# 09_USB_hub.net
KiCad netlist of a schematic drawn in Altium Designer
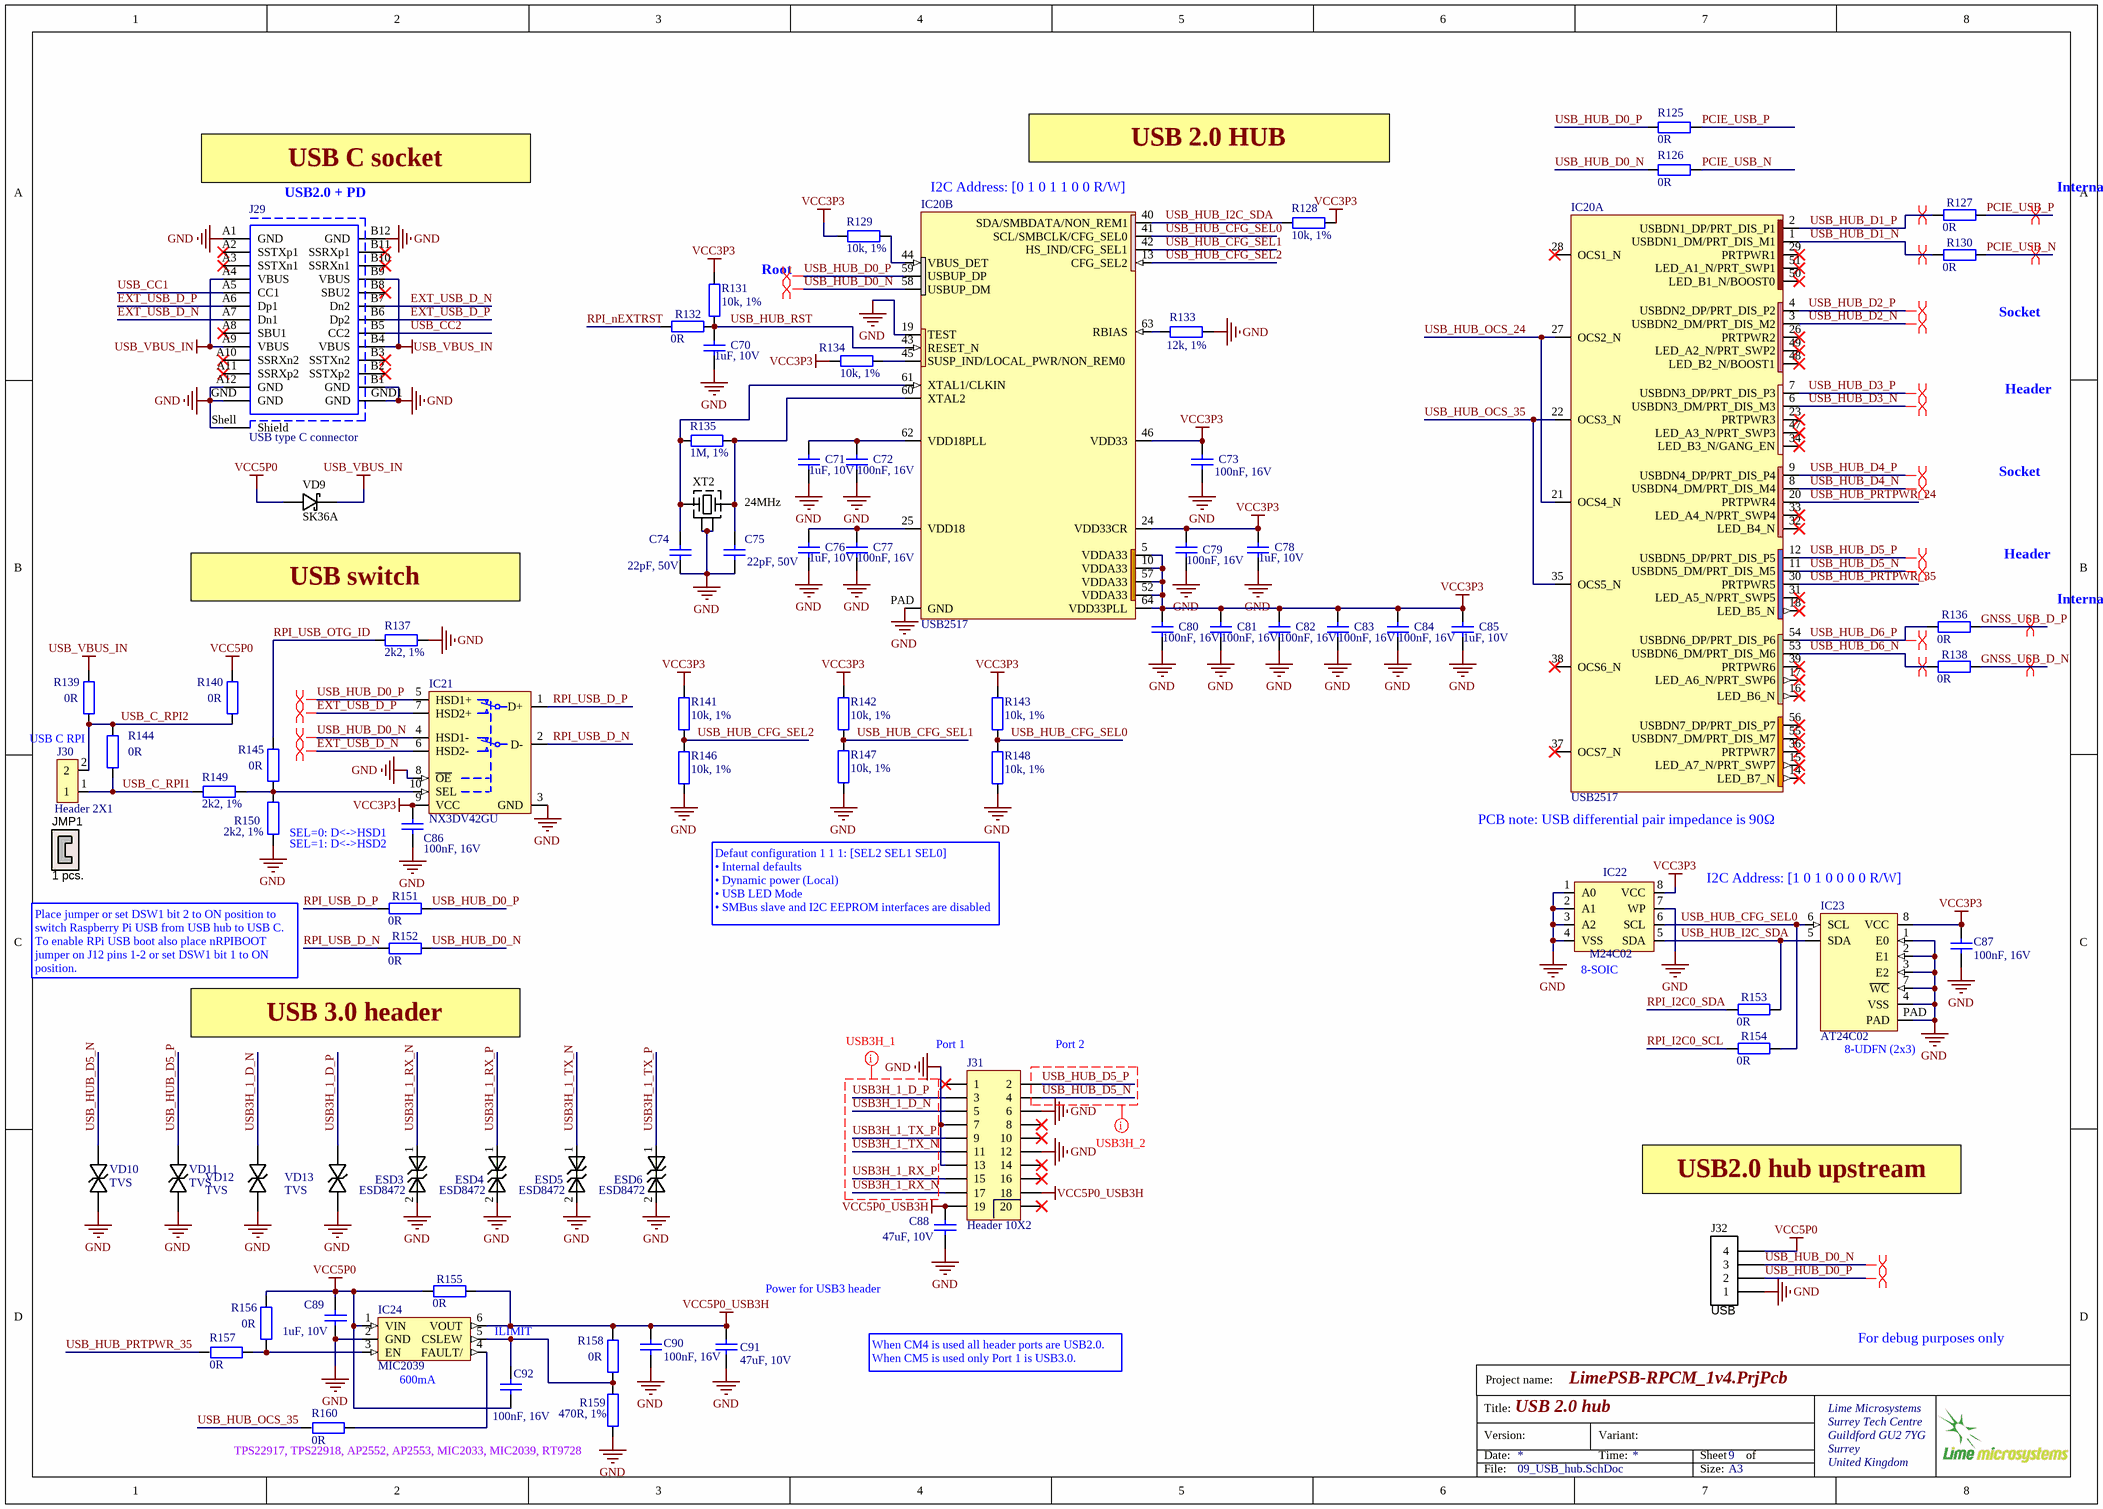
[diagram p0: 09_USB_hub.SchDoc]

(export (version "E")
  (design (tool "Eeschema 10.0.6"))
  (components
    (comp (ref "C70")
      (value "1uF, 10V")
      (footprint "CAP0402")
      (description "CAP CER 1UF 10V X5R 0402")
      (fields (field (name "MANUFACTURER") "Yageo") (field (name "TOLERANCE") "±20%"))
      (libsource (lib "LimeMicroAltiumLib_schLib") (part "Cap_0402"))
    )
    (comp (ref "C71")
      (value "1uF, 10V")
      (footprint "CAP0402")
      (description "CAP CER 1UF 10V X5R 0402")
      (fields (field (name "MANUFACTURER") "Yageo") (field (name "TOLERANCE") "±20%"))
      (libsource (lib "LimeMicroAltiumLib_schLib") (part "Cap_0402"))
    )
    (comp (ref "C72")
      (value "100nF, 16V")
      (footprint "CAP0402")
      (fields
        (field (name "MANUFACTURER") "Murata Electronics")
        (field (name "TOLERANCE") "10 %")
        (field (name "MANUFACTURER PART NUMBER") "GRM155R71C104KA88D")
      )
      (libsource (lib "LimeMicroAltiumLib_schLib") (part "Cap_0402"))
    )
    (comp (ref "C73")
      (value "100nF, 16V")
      (footprint "CAP0402")
      (fields
        (field (name "MANUFACTURER") "Murata Electronics")
        (field (name "TOLERANCE") "10 %")
        (field (name "MANUFACTURER PART NUMBER") "GRM155R71C104KA88D")
      )
      (libsource (lib "LimeMicroAltiumLib_schLib") (part "Cap_0402"))
    )
    (comp (ref "C74")
      (value "22pF, 50V")
      (footprint "CAP0402")
      (fields (field (name "TOLERANCE") "±5%") (field (name "MANUFACTURER") "Yageo"))
      (libsource (lib "LimeMicroAltiumLib_schLib") (part "Cap_0402"))
    )
    (comp (ref "C75")
      (value "22pF, 50V")
      (footprint "CAP0402")
      (fields (field (name "TOLERANCE") "±5%") (field (name "MANUFACTURER") "Yageo"))
      (libsource (lib "LimeMicroAltiumLib_schLib") (part "Cap_0402"))
    )
    (comp (ref "C76")
      (value "1uF, 10V")
      (footprint "CAP0402")
      (description "CAP CER 1UF 10V X5R 0402")
      (fields (field (name "MANUFACTURER") "Yageo") (field (name "TOLERANCE") "±20%"))
      (libsource (lib "LimeMicroAltiumLib_schLib") (part "Cap_0402"))
    )
    (comp (ref "C77")
      (value "100nF, 16V")
      (footprint "CAP0402")
      (fields
        (field (name "MANUFACTURER") "Murata Electronics")
        (field (name "TOLERANCE") "10 %")
        (field (name "MANUFACTURER PART NUMBER") "GRM155R71C104KA88D")
      )
      (libsource (lib "LimeMicroAltiumLib_schLib") (part "Cap_0402"))
    )
    (comp (ref "C78")
      (value "1uF, 10V")
      (footprint "CAP0402")
      (description "CAP CER 1UF 10V X5R 0402")
      (fields (field (name "MANUFACTURER") "Yageo") (field (name "TOLERANCE") "±20%"))
      (libsource (lib "LimeMicroAltiumLib_schLib") (part "Cap_0402"))
    )
    (comp (ref "C79")
      (value "100nF, 16V")
      (footprint "CAP0402")
      (fields
        (field (name "MANUFACTURER") "Murata Electronics")
        (field (name "TOLERANCE") "10 %")
        (field (name "MANUFACTURER PART NUMBER") "GRM155R71C104KA88D")
      )
      (libsource (lib "LimeMicroAltiumLib_schLib") (part "Cap_0402"))
    )
    (comp (ref "C80")
      (value "100nF, 16V")
      (footprint "CAP0402")
      (fields
        (field (name "MANUFACTURER") "Murata Electronics")
        (field (name "TOLERANCE") "10 %")
        (field (name "MANUFACTURER PART NUMBER") "GRM155R71C104KA88D")
      )
      (libsource (lib "LimeMicroAltiumLib_schLib") (part "Cap_0402"))
    )
    (comp (ref "C81")
      (value "100nF, 16V")
      (footprint "CAP0402")
      (fields
        (field (name "MANUFACTURER") "Murata Electronics")
        (field (name "TOLERANCE") "10 %")
        (field (name "MANUFACTURER PART NUMBER") "GRM155R71C104KA88D")
      )
      (libsource (lib "LimeMicroAltiumLib_schLib") (part "Cap_0402"))
    )
    (comp (ref "C82")
      (value "100nF, 16V")
      (footprint "CAP0402")
      (fields
        (field (name "MANUFACTURER") "Murata Electronics")
        (field (name "TOLERANCE") "10 %")
        (field (name "MANUFACTURER PART NUMBER") "GRM155R71C104KA88D")
      )
      (libsource (lib "LimeMicroAltiumLib_schLib") (part "Cap_0402"))
    )
    (comp (ref "C83")
      (value "100nF, 16V")
      (footprint "CAP0402")
      (fields
        (field (name "MANUFACTURER") "Murata Electronics")
        (field (name "TOLERANCE") "10 %")
        (field (name "MANUFACTURER PART NUMBER") "GRM155R71C104KA88D")
      )
      (libsource (lib "LimeMicroAltiumLib_schLib") (part "Cap_0402"))
    )
    (comp (ref "C84")
      (value "100nF, 16V")
      (footprint "CAP0402")
      (fields
        (field (name "MANUFACTURER") "Murata Electronics")
        (field (name "TOLERANCE") "10 %")
        (field (name "MANUFACTURER PART NUMBER") "GRM155R71C104KA88D")
      )
      (libsource (lib "LimeMicroAltiumLib_schLib") (part "Cap_0402"))
    )
    (comp (ref "C85")
      (value "1uF, 10V")
      (footprint "CAP0402")
      (description "CAP CER 1UF 10V X5R 0402")
      (fields (field (name "MANUFACTURER") "Yageo") (field (name "TOLERANCE") "±20%"))
      (libsource (lib "LimeMicroAltiumLib_schLib") (part "Cap_0402"))
    )
    (comp (ref "C86")
      (value "100nF, 16V")
      (footprint "CAP0402")
      (fields
        (field (name "MANUFACTURER") "Murata Electronics")
        (field (name "TOLERANCE") "10 %")
        (field (name "MANUFACTURER PART NUMBER") "GRM155R71C104KA88D")
      )
      (libsource (lib "LimeMicroAltiumLib_schLib") (part "Cap_0402"))
    )
    (comp (ref "C87")
      (value "100nF, 16V")
      (footprint "CAP0402")
      (fields
        (field (name "TOLERANCE") "10 %")
        (field (name "MANUFACTURER") "Murata Electronics")
        (field (name "MANUFACTURER PART NUMBER") "GRM155R71C104KA88D")
      )
      (libsource (lib "LimeFPGAboard_schLib") (part "Cap_0603"))
    )
    (comp (ref "C88")
      (value "47uF, 10V")
      (footprint "CAP1206")
      (fields (field (name "TOLERANCE") "±20%") (field (name "MANUFACTURER") "TDK Corporation"))
      (libsource (lib "LimeFPGAboard_schLib") (part "Cap_1206"))
    )
    (comp (ref "C89")
      (value "1uF, 10V")
      (footprint "CAP0402")
      (fields (field (name "MANUFACTURER") "Yageo"))
      (libsource (lib "") (part "Cap_0402_1"))
    )
    (comp (ref "C90")
      (value "100nF, 16V")
      (footprint "CAP0402")
      (fields
        (field (name "MANUFACTURER") "Murata Electronics")
        (field (name "TOLERANCE") "10 %")
        (field (name "MANUFACTURER PART NUMBER") "GRM155R71C104KA88D")
      )
      (libsource (lib "") (part "Cap_0402_1"))
    )
    (comp (ref "C91")
      (value "47uF, 10V")
      (footprint "CAP1206")
      (fields (field (name "TOLERANCE") "±20%") (field (name "MANUFACTURER") "TDK Corporation"))
      (libsource (lib "LimeFPGAboard_schLib") (part "Cap_1206"))
    )
    (comp (ref "C92")
      (value "100nF, 16V")
      (footprint "CAP0402")
      (fields
        (field (name "MANUFACTURER") "Murata Electronics")
        (field (name "TOLERANCE") "10 %")
        (field (name "MANUFACTURER PART NUMBER") "GRM155R71C104KA88D")
      )
      (libsource (lib "") (part "Cap_0402_1"))
    )
    (comp (ref "ESD3")
      (value "ESD8472")
      (footprint "ESD8472_X3DFN2")
      (fields (field (name "MANUFACTURER") "ON Semiconductor"))
      (libsource (lib "LimeMicroAltiumLib_schLib") (part "ESD8472"))
    )
    (comp (ref "ESD4")
      (value "ESD8472")
      (footprint "ESD8472_X3DFN2")
      (fields (field (name "MANUFACTURER") "ON Semiconductor"))
      (libsource (lib "LimeMicroAltiumLib_schLib") (part "ESD8472"))
    )
    (comp (ref "ESD5")
      (value "ESD8472")
      (footprint "ESD8472_X3DFN2")
      (fields (field (name "MANUFACTURER") "ON Semiconductor"))
      (libsource (lib "LimeMicroAltiumLib_schLib") (part "ESD8472"))
    )
    (comp (ref "ESD6")
      (value "ESD8472")
      (footprint "ESD8472_X3DFN2")
      (fields (field (name "MANUFACTURER") "ON Semiconductor"))
      (libsource (lib "LimeMicroAltiumLib_schLib") (part "ESD8472"))
    )
    (comp (ref "IC20")
      (value "USB2517")
      (footprint "USB2517-JZX-TR_USB_HUB_QFN64")
      (fields (field (name "MANUFACTURER") "Microchip"))
      (libsource (lib "LimeMicroAltiumLib_schLib_r05") (part "USB2517-JZX-TR_USB_HUB"))
    )
    (comp (ref "IC21")
      (value "NX3DV42GU")
      (footprint "FSUSB42UMX")
      (fields (field (name "MANUFACTURER") "NXP Semiconductors"))
      (libsource (lib "LimeMicroAltiumLib_schLib_r01") (part "FSUSB42UMX"))
    )
    (comp (ref "IC22")
      (value "M24C02")
      (footprint "SOIC127P600-8DL_v2")
      (fields (field (name "MANUFACTURER") "STMicroelectronics"))
      (libsource (lib "LimeMicroAltiumLib_schLib") (part "24FC64F"))
    )
    (comp (ref "IC23")
      (value "AT24C02")
      (footprint "M24128-DFMC6TG")
      (fields (field (name "MANUFACTURER") "Microchip"))
      (libsource (lib "LimeMicroAltiumLib_schLib") (part "M24128-DFMC6TG"))
    )
    (comp (ref "IC24")
      (value "MIC2039")
      (footprint "SOT23-6")
      (fields (field (name "MANUFACTURER") "Microchip"))
      (libsource (lib "LimeMicroAltiumLib_schLib_r04") (part "MIC2033_power_switch"))
    )
    (comp (ref "J29")
      (value "USB type C connector")
      (footprint "DUAL_USB-C_632723100011")
      (fields (field (name "MANUFACTURER") "Wurth Electronics"))
      (libsource (lib "LimeMicroAltiumLib_schLib_r04") (part "DUAL_USB-C_632723100011"))
    )
    (comp (ref "J30")
      (value "Header 2X1")
      (footprint "HDR_1x2")
      (fields (field (name "MANUFACTURER") "3M"))
      (libsource (lib "LimeFPGAboard_schLib") (part "Jumper"))
    )
    (comp (ref "J31")
      (value "Header 10X2")
      (footprint "Header10x2_TH_2MM")
      (description "Header, 10-Pin, Dual row")
      (fields (field (name "MANUFACTURER") "Amphenol"))
      (libsource (lib "LimeMicroAltiumLib") (part "Header 10X2"))
    )
    (comp (ref "J32")
      (value "USB")
      (footprint "HEADER4X1_TH")
      (description "Header, 4-pin")
      (fields (field (name "MANUFACTURER") "Wurth Electronics Inc."))
      (libsource (lib "LimeMicroAltiumLib_schLib") (part "Header4P"))
    )
    (comp (ref "JMP1")
      (value "1 pcs.")
      (description "Shorting Jumper, 2-position, 1.27mm pitch")
      (fields (field (name "MANUFACTURER") "Sullins"))
      (libsource (lib "LimeMicroAltiumLib_schLib") (part "JUMP_2P_CONN_HEADER"))
    )
    (comp (ref "R125")
      (value "0R")
      (footprint "RES0402")
      (fields (field (name "MANUFACTURER") "Yageo") (field (name "TOLERANCE") "Jumper"))
      (libsource (lib "LimeMicroAltiumLib_schLib") (part "Res_0402"))
    )
    (comp (ref "R126")
      (value "0R")
      (footprint "RES0402")
      (fields (field (name "MANUFACTURER") "Yageo") (field (name "TOLERANCE") "Jumper"))
      (libsource (lib "LimeMicroAltiumLib_schLib") (part "Res_0402"))
    )
    (comp (ref "R127")
      (value "0R")
      (footprint "RES0402")
      (fields (field (name "MANUFACTURER") "Yageo") (field (name "TOLERANCE") "Jumper"))
      (libsource (lib "") (part "Res_0402_1"))
    )
    (comp (ref "R128")
      (value "10k, 1%")
      (footprint "RES0402")
      (fields (field (name "MANUFACTURER") "Yageo") (field (name "TOLERANCE") "±1%"))
      (libsource (lib "LimeMicroAltiumLib_schLib") (part "Res_0402"))
    )
    (comp (ref "R129")
      (value "10k, 1%")
      (footprint "RES0402")
      (fields (field (name "MANUFACTURER") "Yageo") (field (name "TOLERANCE") "±1%"))
      (libsource (lib "LimeMicroAltiumLib_schLib") (part "Res_0402"))
    )
    (comp (ref "R130")
      (value "0R")
      (footprint "RES0402")
      (fields (field (name "MANUFACTURER") "Yageo") (field (name "TOLERANCE") "Jumper"))
      (libsource (lib "") (part "Res_0402_1"))
    )
    (comp (ref "R131")
      (value "10k, 1%")
      (footprint "RES0402")
      (fields (field (name "MANUFACTURER") "Yageo") (field (name "TOLERANCE") "±1%"))
      (libsource (lib "LimeMicroAltiumLib_schLib") (part "Res_0402"))
    )
    (comp (ref "R132")
      (value "0R")
      (footprint "RES0402")
      (fields (field (name "MANUFACTURER") "Yageo") (field (name "TOLERANCE") "Jumper"))
      (libsource (lib "") (part "Res_0402_1"))
    )
    (comp (ref "R133")
      (value "12k, 1%")
      (footprint "RES0402")
      (fields (field (name "MANUFACTURER") "Samsung Electro-Mechanics") (field (name "TOLERANCE") "±1%"))
      (libsource (lib "LimeMicroAltiumLib_schLib") (part "Res_0402"))
    )
    (comp (ref "R134")
      (value "10k, 1%")
      (footprint "RES0402")
      (fields (field (name "MANUFACTURER") "Yageo") (field (name "TOLERANCE") "±1%"))
      (libsource (lib "LimeMicroAltiumLib_schLib") (part "Res_0402"))
    )
    (comp (ref "R135")
      (value "1M, 1%")
      (footprint "RES0402")
      (fields (field (name "TOLERANCE") "±1%") (field (name "MANUFACTURER") "Yageo"))
      (libsource (lib "LimeMicroAltiumLib_schLib") (part "Res_0402"))
    )
    (comp (ref "R136")
      (value "0R")
      (footprint "RES0402")
      (fields (field (name "MANUFACTURER") "Yageo") (field (name "TOLERANCE") "Jumper"))
      (libsource (lib "") (part "Res_0402_1"))
    )
    (comp (ref "R137")
      (value "2k2, 1%")
      (footprint "RES0402")
      (fields (field (name "MANUFACTURER") "Stackpole Electronics Inc") (field (name "TOLERANCE") "±1%"))
      (libsource (lib "LimeMicroAltiumLib_schLib") (part "Res_0402"))
    )
    (comp (ref "R138")
      (value "0R")
      (footprint "RES0402")
      (fields (field (name "MANUFACTURER") "Yageo") (field (name "TOLERANCE") "Jumper"))
      (libsource (lib "") (part "Res_0402_1"))
    )
    (comp (ref "R139")
      (value "0R")
      (footprint "RES0402")
      (fields (field (name "MANUFACTURER") "Yageo") (field (name "TOLERANCE") "Jumper"))
      (libsource (lib "") (part "Res_0402_1"))
    )
    (comp (ref "R140")
      (value "0R")
      (footprint "RES0402")
      (fields (field (name "MANUFACTURER") "Yageo") (field (name "TOLERANCE") "Jumper"))
      (libsource (lib "") (part "Res_0402_1"))
    )
    (comp (ref "R141")
      (value "10k, 1%")
      (footprint "RES0402")
      (fields (field (name "MANUFACTURER") "Yageo") (field (name "TOLERANCE") "±1%"))
      (libsource (lib "LimeMicroAltiumLib_schLib") (part "Res_0402"))
    )
    (comp (ref "R142")
      (value "10k, 1%")
      (footprint "RES0402")
      (fields (field (name "MANUFACTURER") "Yageo") (field (name "TOLERANCE") "±1%"))
      (libsource (lib "LimeMicroAltiumLib_schLib") (part "Res_0402"))
    )
    (comp (ref "R143")
      (value "10k, 1%")
      (footprint "RES0402")
      (fields (field (name "MANUFACTURER") "Yageo") (field (name "TOLERANCE") "±1%"))
      (libsource (lib "LimeMicroAltiumLib_schLib") (part "Res_0402"))
    )
    (comp (ref "R144")
      (value "0R")
      (footprint "RES0402")
      (fields (field (name "MANUFACTURER") "Yageo") (field (name "TOLERANCE") "Jumper"))
      (libsource (lib "") (part "Res_0402_1"))
    )
    (comp (ref "R145")
      (value "0R")
      (footprint "RES0402")
      (fields (field (name "MANUFACTURER") "Yageo") (field (name "TOLERANCE") "Jumper"))
      (libsource (lib "") (part "Res_0402_1"))
    )
    (comp (ref "R146")
      (value "10k, 1%")
      (footprint "RES0402")
      (fields (field (name "MANUFACTURER") "Yageo") (field (name "TOLERANCE") "±1%"))
      (libsource (lib "LimeMicroAltiumLib_schLib") (part "Res_0402"))
    )
    (comp (ref "R147")
      (value "10k, 1%")
      (footprint "RES0402")
      (fields (field (name "MANUFACTURER") "Yageo") (field (name "TOLERANCE") "±1%"))
      (libsource (lib "LimeMicroAltiumLib_schLib") (part "Res_0402"))
    )
    (comp (ref "R148")
      (value "10k, 1%")
      (footprint "RES0402")
      (fields (field (name "MANUFACTURER") "Yageo") (field (name "TOLERANCE") "±1%"))
      (libsource (lib "LimeMicroAltiumLib_schLib") (part "Res_0402"))
    )
    (comp (ref "R149")
      (value "2k2, 1%")
      (footprint "RES0402")
      (fields (field (name "MANUFACTURER") "Stackpole Electronics Inc") (field (name "TOLERANCE") "±1%"))
      (libsource (lib "LimeMicroAltiumLib_schLib") (part "Res_0402"))
    )
    (comp (ref "R150")
      (value "2k2, 1%")
      (footprint "RES0402")
      (fields (field (name "MANUFACTURER") "Stackpole Electronics Inc") (field (name "TOLERANCE") "±1%"))
      (libsource (lib "LimeMicroAltiumLib_schLib") (part "Res_0402"))
    )
    (comp (ref "R151")
      (value "0R")
      (footprint "RES0402")
      (fields (field (name "MANUFACTURER") "Yageo") (field (name "TOLERANCE") "Jumper"))
      (libsource (lib "") (part "Res_0402_1"))
    )
    (comp (ref "R152")
      (value "0R")
      (footprint "RES0402")
      (fields (field (name "MANUFACTURER") "Yageo") (field (name "TOLERANCE") "Jumper"))
      (libsource (lib "") (part "Res_0402_1"))
    )
    (comp (ref "R153")
      (value "0R")
      (footprint "RES0402")
      (fields (field (name "MANUFACTURER") "Yageo") (field (name "TOLERANCE") "Jumper"))
      (libsource (lib "") (part "Res_0402_1"))
    )
    (comp (ref "R154")
      (value "0R")
      (footprint "RES0402")
      (fields (field (name "MANUFACTURER") "Yageo") (field (name "TOLERANCE") "Jumper"))
      (libsource (lib "") (part "Res_0402_1"))
    )
    (comp (ref "R155")
      (value "0R")
      (footprint "RES0402")
      (fields (field (name "MANUFACTURER") "Yageo") (field (name "TOLERANCE") "Jumper"))
      (libsource (lib "") (part "Res_0402_1"))
    )
    (comp (ref "R156")
      (value "0R")
      (footprint "RES0402")
      (fields (field (name "MANUFACTURER") "Yageo") (field (name "TOLERANCE") "Jumper"))
      (libsource (lib "") (part "Res_0402_1"))
    )
    (comp (ref "R157")
      (value "0R")
      (footprint "RES0402")
      (fields (field (name "MANUFACTURER") "Yageo") (field (name "TOLERANCE") "Jumper"))
      (libsource (lib "") (part "Res_0402_1"))
    )
    (comp (ref "R158")
      (value "0R")
      (footprint "RES0402")
      (fields (field (name "MANUFACTURER") "Yageo") (field (name "TOLERANCE") "Jumper"))
      (libsource (lib "") (part "Res_0402_1"))
    )
    (comp (ref "R159")
      (value "470R, 1%")
      (footprint "RES0402")
      (fields (field (name "TOLERANCE") "1%") (field (name "MANUFACTURER") "Yageo"))
      (libsource (lib "") (part "Res_0402_1"))
    )
    (comp (ref "R160")
      (value "0R")
      (footprint "RES0402")
      (fields (field (name "MANUFACTURER") "Yageo") (field (name "TOLERANCE") "Jumper"))
      (libsource (lib "") (part "Res_0402_1"))
    )
    (comp (ref "VD9")
      (value "SK36A")
      (footprint "SK32A-L_DIODE_DO-214AC")
      (description "Diode Schottky SMD SOD-523F")
      (fields (field (name "MANUFACTURER") "Micro Commercial Co"))
      (libsource (lib "LimeMicroAltiumLib_schLib") (part "DIODE_SCHOTTKY_SOD-523F"))
    )
    (comp (ref "VD10")
      (value "TVS")
      (footprint "SOD323")
      (fields
        (field (name "MANUFACTURER PART NUMBER") "SD03LCC")
        (field (name "MANUFACTURER") "Sangdest Microelectronics")
      )
      (libsource (lib "LimeNet-Micro_2v1-SDR") (part "DIODE_TVS"))
    )
    (comp (ref "VD11")
      (value "TVS")
      (footprint "SOD323")
      (fields
        (field (name "MANUFACTURER PART NUMBER") "SD03LCC")
        (field (name "MANUFACTURER") "Sangdest Microelectronics")
      )
      (libsource (lib "LimeNet-Micro_2v1-SDR") (part "DIODE_TVS"))
    )
    (comp (ref "VD12")
      (value "TVS")
      (footprint "SOD323")
      (fields
        (field (name "MANUFACTURER PART NUMBER") "SD03LCC")
        (field (name "MANUFACTURER") "Sangdest Microelectronics")
      )
      (libsource (lib "LimeNet-Micro_2v1-SDR") (part "DIODE_TVS"))
    )
    (comp (ref "VD13")
      (value "TVS")
      (footprint "SOD323")
      (fields
        (field (name "MANUFACTURER PART NUMBER") "SD03LCC")
        (field (name "MANUFACTURER") "Sangdest Microelectronics")
      )
      (libsource (lib "LimeNet-Micro_2v1-SDR") (part "DIODE_TVS"))
    )
    (comp (ref "XT2")
      (value "24MHz")
      (footprint "CRYSTAL_4-LCC")
      (description "Oscillator Crystal 25 MHz")
      (fields (field (name "MANUFACTURER") "Abracon"))
      (libsource (lib "LimeFPGAboard_schLib") (part "CRYSTAL_19M2"))
    )
  )
  (nets
    (net (code "2") (name "/EXT_USB_D_N") (class "Default")
      (node (ref "IC21") (pin "6") (pinfunction "HSD2-_6") (pintype "passive"))
      (node (ref "J29") (pin "A7") (pinfunction "Dn1_A7") (pintype "passive"))
      (node (ref "J29") (pin "B7") (pinfunction "Dn2_B7") (pintype "passive"))
    )
    (net (code "3") (name "/EXT_USB_D_P") (class "Default")
      (node (ref "IC21") (pin "7") (pinfunction "HSD2+_7") (pintype "passive"))
      (node (ref "J29") (pin "A6") (pinfunction "Dp1_A6") (pintype "passive"))
      (node (ref "J29") (pin "B6") (pinfunction "Dp2_B6") (pintype "passive"))
    )
    (net (code "4") (name "/GNSS_USB_D_N") (class "Default")
      (node (ref "R138") (pin "1") (pinfunction "1_1") (pintype "passive"))
    )
    (net (code "5") (name "/GNSS_USB_D_P") (class "Default")
      (node (ref "R136") (pin "1") (pinfunction "1_1") (pintype "passive"))
    )
    (net (code "6") (name "/PCIE_USB_N") (class "Default")
      (node (ref "R126") (pin "2") (pinfunction "2_2") (pintype "passive"))
      (node (ref "R130") (pin "1") (pinfunction "1_1") (pintype "passive"))
    )
    (net (code "7") (name "/PCIE_USB_P") (class "Default")
      (node (ref "R125") (pin "2") (pinfunction "2_2") (pintype "passive"))
      (node (ref "R127") (pin "1") (pinfunction "1_1") (pintype "passive"))
    )
    (net (code "8") (name "/RPI_I2C0_SCL") (class "Default")
      (node (ref "R154") (pin "2") (pinfunction "2_2") (pintype "passive"))
    )
    (net (code "9") (name "/RPI_I2C0_SDA") (class "Default")
      (node (ref "R153") (pin "2") (pinfunction "2_2") (pintype "passive"))
    )
    (net (code "10") (name "/RPI_USB_D_N") (class "Default")
      (node (ref "IC21") (pin "2") (pinfunction "D-_2") (pintype "passive"))
      (node (ref "R152") (pin "2") (pinfunction "2_2") (pintype "passive"))
    )
    (net (code "11") (name "/RPI_USB_D_P") (class "Default")
      (node (ref "IC21") (pin "1") (pinfunction "D+_1") (pintype "passive"))
      (node (ref "R151") (pin "2") (pinfunction "2_2") (pintype "passive"))
    )
    (net (code "12") (name "/RPI_USB_OTG_ID") (class "Default")
      (node (ref "R137") (pin "1") (pinfunction "1_1") (pintype "passive"))
      (node (ref "R145") (pin "2") (pinfunction "2_2") (pintype "passive"))
    )
    (net (code "13") (name "/RPI_nEXTRST") (class "Default")
      (node (ref "R132") (pin "2") (pinfunction "2_2") (pintype "passive"))
    )
    (net (code "14") (name "/USB3H_1_D_N") (class "Default")
      (node (ref "J31") (pin "5") (pinfunction "5_5") (pintype "passive"))
      (node (ref "VD12") (pin "A") (pinfunction "A_A") (pintype "passive"))
    )
    (net (code "15") (name "/USB3H_1_D_P") (class "Default")
      (node (ref "J31") (pin "3") (pinfunction "3_3") (pintype "passive"))
      (node (ref "VD13") (pin "A") (pinfunction "A_A") (pintype "passive"))
    )
    (net (code "16") (name "/USB3H_1_RX_N") (class "Default")
      (node (ref "ESD3") (pin "1") (pinfunction "1_1") (pintype "passive"))
      (node (ref "J31") (pin "17") (pinfunction "17_17") (pintype "passive"))
    )
    (net (code "17") (name "/USB3H_1_RX_P") (class "Default")
      (node (ref "ESD4") (pin "1") (pinfunction "1_1") (pintype "passive"))
      (node (ref "J31") (pin "15") (pinfunction "15_15") (pintype "passive"))
    )
    (net (code "18") (name "/USB3H_1_TX_N") (class "Default")
      (node (ref "ESD5") (pin "1") (pinfunction "1_1") (pintype "passive"))
      (node (ref "J31") (pin "11") (pinfunction "11_11") (pintype "passive"))
    )
    (net (code "19") (name "/USB3H_1_TX_P") (class "Default")
      (node (ref "ESD6") (pin "1") (pinfunction "1_1") (pintype "passive"))
      (node (ref "J31") (pin "9") (pinfunction "9_9") (pintype "passive"))
    )
    (net (code "20") (name "/USB_CC1") (class "Default")
      (node (ref "J29") (pin "A5") (pinfunction "CC1_A5") (pintype "passive"))
    )
    (net (code "21") (name "/USB_CC2") (class "Default")
      (node (ref "J29") (pin "B5") (pinfunction "CC2_B5") (pintype "passive"))
    )
    (net (code "22") (name "/USB_C_RPI1") (class "Default")
      (node (ref "J30") (pin "1") (pinfunction "1_1") (pintype "passive"))
      (node (ref "R144") (pin "1") (pinfunction "1_1") (pintype "passive"))
      (node (ref "R149") (pin "1") (pinfunction "1_1") (pintype "passive"))
    )
    (net (code "23") (name "/USB_C_RPI2") (class "Default")
      (node (ref "J30") (pin "2") (pinfunction "2_2") (pintype "passive"))
      (node (ref "R139") (pin "1") (pinfunction "1_1") (pintype "passive"))
      (node (ref "R140") (pin "1") (pinfunction "1_1") (pintype "passive"))
      (node (ref "R144") (pin "2") (pinfunction "2_2") (pintype "passive"))
    )
    (net (code "24") (name "/USB_HUB_CFG_SEL0") (class "Default")
      (node (ref "IC20") (pin "41") (pinfunction "SCL/SMBCLK/CFG_SEL0_41") (pintype "bidirectional"))
      (node (ref "IC22") (pin "6") (pinfunction "SCL_6") (pintype "passive"))
      (node (ref "IC23") (pin "6") (pinfunction "SCL_6") (pintype "input"))
      (node (ref "R143") (pin "1") (pinfunction "1_1") (pintype "passive"))
      (node (ref "R148") (pin "2") (pinfunction "2_2") (pintype "passive"))
      (node (ref "R154") (pin "1") (pinfunction "1_1") (pintype "passive"))
    )
    (net (code "25") (name "/USB_HUB_CFG_SEL1") (class "Default")
      (node (ref "IC20") (pin "42") (pinfunction "HS_IND/CFG_SEL1_42") (pintype "bidirectional"))
      (node (ref "R142") (pin "1") (pinfunction "1_1") (pintype "passive"))
      (node (ref "R147") (pin "1") (pinfunction "1_1") (pintype "passive"))
    )
    (net (code "26") (name "/USB_HUB_CFG_SEL2") (class "Default")
      (node (ref "IC20") (pin "13") (pinfunction "CFG_SEL2_13") (pintype "input"))
      (node (ref "R141") (pin "1") (pinfunction "1_1") (pintype "passive"))
      (node (ref "R146") (pin "2") (pinfunction "2_2") (pintype "passive"))
    )
    (net (code "27") (name "/USB_HUB_D0_N") (class "Default")
      (node (ref "IC20") (pin "58") (pinfunction "USBUP_DM_58") (pintype "bidirectional"))
      (node (ref "IC21") (pin "4") (pinfunction "HSD1-_4") (pintype "passive"))
      (node (ref "J32") (pin "3") (pinfunction "3_3") (pintype "passive"))
      (node (ref "R126") (pin "1") (pinfunction "1_1") (pintype "passive"))
      (node (ref "R152") (pin "1") (pinfunction "1_1") (pintype "passive"))
    )
    (net (code "28") (name "/USB_HUB_D0_P") (class "Default")
      (node (ref "IC20") (pin "59") (pinfunction "USBUP_DP_59") (pintype "bidirectional"))
      (node (ref "IC21") (pin "5") (pinfunction "HSD1+_5") (pintype "passive"))
      (node (ref "J32") (pin "2") (pinfunction "2_2") (pintype "passive"))
      (node (ref "R125") (pin "1") (pinfunction "1_1") (pintype "passive"))
      (node (ref "R151") (pin "1") (pinfunction "1_1") (pintype "passive"))
    )
    (net (code "29") (name "/USB_HUB_D1_N") (class "Default")
      (node (ref "IC20") (pin "1") (pinfunction "USBDN1_DM/PRT_DIS_M1_1") (pintype "bidirectional"))
      (node (ref "R130") (pin "2") (pinfunction "2_2") (pintype "passive"))
    )
    (net (code "30") (name "/USB_HUB_D1_P") (class "Default")
      (node (ref "IC20") (pin "2") (pinfunction "USBDN1_DP/PRT_DIS_P1_2") (pintype "bidirectional"))
      (node (ref "R127") (pin "2") (pinfunction "2_2") (pintype "passive"))
    )
    (net (code "31") (name "/USB_HUB_D2_N") (class "Default")
      (node (ref "IC20") (pin "3") (pinfunction "USBDN2_DM/PRT_DIS_M2_3") (pintype "bidirectional"))
    )
    (net (code "32") (name "/USB_HUB_D2_P") (class "Default")
      (node (ref "IC20") (pin "4") (pinfunction "USBDN2_DP/PRT_DIS_P2_4") (pintype "bidirectional"))
    )
    (net (code "33") (name "/USB_HUB_D3_N") (class "Default")
      (node (ref "IC20") (pin "6") (pinfunction "USBDN3_DM/PRT_DIS_M3_6") (pintype "bidirectional"))
    )
    (net (code "34") (name "/USB_HUB_D3_P") (class "Default")
      (node (ref "IC20") (pin "7") (pinfunction "USBDN3_DP/PRT_DIS_P3_7") (pintype "bidirectional"))
    )
    (net (code "35") (name "/USB_HUB_D4_N") (class "Default")
      (node (ref "IC20") (pin "8") (pinfunction "USBDN4_DM/PRT_DIS_M4_8") (pintype "bidirectional"))
    )
    (net (code "36") (name "/USB_HUB_D4_P") (class "Default")
      (node (ref "IC20") (pin "9") (pinfunction "USBDN4_DP/PRT_DIS_P4_9") (pintype "bidirectional"))
    )
    (net (code "37") (name "/USB_HUB_D5_N") (class "Default")
      (node (ref "IC20") (pin "11") (pinfunction "USBDN5_DM/PRT_DIS_M5_11") (pintype "bidirectional"))
      (node (ref "J31") (pin "4") (pinfunction "4_4") (pintype "passive"))
      (node (ref "VD10") (pin "A") (pinfunction "A_A") (pintype "passive"))
    )
    (net (code "38") (name "/USB_HUB_D5_P") (class "Default")
      (node (ref "IC20") (pin "12") (pinfunction "USBDN5_DP/PRT_DIS_P5_12") (pintype "bidirectional"))
      (node (ref "J31") (pin "2") (pinfunction "2_2") (pintype "passive"))
      (node (ref "VD11") (pin "A") (pinfunction "A_A") (pintype "passive"))
    )
    (net (code "39") (name "/USB_HUB_D6_N") (class "Default")
      (node (ref "IC20") (pin "53") (pinfunction "USBDN6_DM/PRT_DIS_M6_53") (pintype "bidirectional"))
      (node (ref "R138") (pin "2") (pinfunction "2_2") (pintype "passive"))
    )
    (net (code "40") (name "/USB_HUB_D6_P") (class "Default")
      (node (ref "IC20") (pin "54") (pinfunction "USBDN6_DP/PRT_DIS_P6_54") (pintype "bidirectional"))
      (node (ref "R136") (pin "2") (pinfunction "2_2") (pintype "passive"))
    )
    (net (code "41") (name "/USB_HUB_I2C_SDA") (class "Default")
      (node (ref "IC20") (pin "40") (pinfunction "SDA/SMBDATA/NON_REM1_40") (pintype "bidirectional"))
      (node (ref "IC22") (pin "5") (pinfunction "SDA_5") (pintype "passive"))
      (node (ref "IC23") (pin "5") (pinfunction "SDA_5") (pintype "bidirectional"))
      (node (ref "R128") (pin "1") (pinfunction "1_1") (pintype "passive"))
      (node (ref "R153") (pin "1") (pinfunction "1_1") (pintype "passive"))
    )
    (net (code "42") (name "/USB_HUB_OCS_24") (class "Default")
      (node (ref "IC20") (pin "21") (pinfunction "OCS4_N_21") (pintype "passive"))
      (node (ref "IC20") (pin "27") (pinfunction "OCS2_N_27") (pintype "passive"))
    )
    (net (code "43") (name "/USB_HUB_OCS_35") (class "Default")
      (node (ref "IC20") (pin "22") (pinfunction "OCS3_N_22") (pintype "passive"))
      (node (ref "IC20") (pin "35") (pinfunction "OCS5_N_35") (pintype "passive"))
      (node (ref "R160") (pin "2") (pinfunction "2_2") (pintype "passive"))
    )
    (net (code "44") (name "/USB_HUB_PRTPWR_24") (class "Default")
      (node (ref "IC20") (pin "20") (pinfunction "PRTPWR4_20") (pintype "passive"))
    )
    (net (code "45") (name "/USB_HUB_PRTPWR_35") (class "Default")
      (node (ref "IC20") (pin "30") (pinfunction "PRTPWR5_30") (pintype "passive"))
      (node (ref "R157") (pin "2") (pinfunction "2_2") (pintype "passive"))
    )
    (net (code "46") (name "/USB_HUB_RST") (class "Default")
      (node (ref "C70") (pin "2") (pinfunction "2_2") (pintype "passive"))
      (node (ref "IC20") (pin "43") (pinfunction "RESET_N_43") (pintype "input"))
      (node (ref "R131") (pin "1") (pinfunction "1_1") (pintype "passive"))
      (node (ref "R132") (pin "1") (pinfunction "1_1") (pintype "passive"))
    )
    (net (code "47") (name "GND") (class "Default")
      (node (ref "C70") (pin "1") (pinfunction "1_1") (pintype "passive"))
      (node (ref "C71") (pin "1") (pinfunction "1_1") (pintype "passive"))
      (node (ref "C72") (pin "2") (pinfunction "2_2") (pintype "passive"))
      (node (ref "C73") (pin "2") (pinfunction "2_2") (pintype "passive"))
      (node (ref "C74") (pin "1") (pinfunction "1_1") (pintype "passive"))
      (node (ref "C75") (pin "1") (pinfunction "1_1") (pintype "passive"))
      (node (ref "C76") (pin "1") (pinfunction "1_1") (pintype "passive"))
      (node (ref "C77") (pin "2") (pinfunction "2_2") (pintype "passive"))
      (node (ref "C78") (pin "1") (pinfunction "1_1") (pintype "passive"))
      (node (ref "C79") (pin "2") (pinfunction "2_2") (pintype "passive"))
      (node (ref "C80") (pin "2") (pinfunction "2_2") (pintype "passive"))
      (node (ref "C81") (pin "2") (pinfunction "2_2") (pintype "passive"))
      (node (ref "C82") (pin "2") (pinfunction "2_2") (pintype "passive"))
      (node (ref "C83") (pin "2") (pinfunction "2_2") (pintype "passive"))
      (node (ref "C84") (pin "2") (pinfunction "2_2") (pintype "passive"))
      (node (ref "C85") (pin "1") (pinfunction "1_1") (pintype "passive"))
      (node (ref "C86") (pin "2") (pinfunction "2_2") (pintype "passive"))
      (node (ref "C87") (pin "2") (pinfunction "2_2") (pintype "passive"))
      (node (ref "C88") (pin "1") (pinfunction "1_1") (pintype "passive"))
      (node (ref "C89") (pin "2") (pinfunction "2_2") (pintype "passive"))
      (node (ref "C90") (pin "2") (pinfunction "2_2") (pintype "passive"))
      (node (ref "C91") (pin "1") (pinfunction "1_1") (pintype "passive"))
      (node (ref "ESD3") (pin "2") (pinfunction "2_2") (pintype "passive"))
      (node (ref "ESD4") (pin "2") (pinfunction "2_2") (pintype "passive"))
      (node (ref "ESD5") (pin "2") (pinfunction "2_2") (pintype "passive"))
      (node (ref "ESD6") (pin "2") (pinfunction "2_2") (pintype "passive"))
      (node (ref "IC20") (pin "19") (pinfunction "TEST_19") (pintype "passive"))
      (node (ref "IC20") (pin "PAD") (pinfunction "GND_PAD") (pintype "power_in"))
      (node (ref "IC21") (pin "3") (pinfunction "GND_3") (pintype "passive"))
      (node (ref "IC21") (pin "8") (pinfunction "~{OE}_8") (pintype "input"))
      (node (ref "IC22") (pin "1") (pinfunction "A0_1") (pintype "passive"))
      (node (ref "IC22") (pin "2") (pinfunction "A1_2") (pintype "passive"))
      (node (ref "IC22") (pin "3") (pinfunction "A2_3") (pintype "passive"))
      (node (ref "IC22") (pin "4") (pinfunction "VSS_4") (pintype "passive"))
      (node (ref "IC22") (pin "7") (pinfunction "WP_7") (pintype "passive"))
      (node (ref "IC23") (pin "1") (pinfunction "E0_1") (pintype "input"))
      (node (ref "IC23") (pin "2") (pinfunction "E1_2") (pintype "input"))
      (node (ref "IC23") (pin "3") (pinfunction "E2_3") (pintype "input"))
      (node (ref "IC23") (pin "4") (pinfunction "VSS_4") (pintype "power_in"))
      (node (ref "IC23") (pin "7") (pinfunction "~{WC}_7") (pintype "input"))
      (node (ref "IC23") (pin "PAD") (pinfunction "PAD_PAD") (pintype "power_in"))
      (node (ref "IC24") (pin "2") (pinfunction "GND_2") (pintype "passive"))
      (node (ref "J29") (pin "A1") (pinfunction "GND_A1") (pintype "passive"))
      (node (ref "J29") (pin "A12") (pinfunction "GND_A12") (pintype "passive"))
      (node (ref "J29") (pin "B1") (pinfunction "GND_B1") (pintype "passive"))
      (node (ref "J29") (pin "B12") (pinfunction "GND_B12") (pintype "passive"))
      (node (ref "J29") (pin "GND") (pinfunction "GND_GND") (pintype "passive"))
      (node (ref "J29") (pin "GND1") (pinfunction "GND_GND1") (pintype "passive"))
      (node (ref "J29") (pin "Shell") (pinfunction "Shield_Shell") (pintype "passive"))
      (node (ref "J31") (pin "12") (pinfunction "12_12") (pintype "passive"))
      (node (ref "J31") (pin "13") (pinfunction "13_13") (pintype "passive"))
      (node (ref "J31") (pin "6") (pinfunction "6_6") (pintype "passive"))
      (node (ref "J31") (pin "7") (pinfunction "7_7") (pintype "passive"))
      (node (ref "J32") (pin "1") (pinfunction "1_1") (pintype "passive"))
      (node (ref "R133") (pin "2") (pinfunction "2_2") (pintype "passive"))
      (node (ref "R137") (pin "2") (pinfunction "2_2") (pintype "passive"))
      (node (ref "R146") (pin "1") (pinfunction "1_1") (pintype "passive"))
      (node (ref "R147") (pin "2") (pinfunction "2_2") (pintype "passive"))
      (node (ref "R148") (pin "1") (pinfunction "1_1") (pintype "passive"))
      (node (ref "R150") (pin "2") (pinfunction "2_2") (pintype "passive"))
      (node (ref "R159") (pin "1") (pinfunction "1_1") (pintype "passive"))
      (node (ref "VD10") (pin "K") (pinfunction "K_K") (pintype "passive"))
      (node (ref "VD11") (pin "K") (pinfunction "K_K") (pintype "passive"))
      (node (ref "VD12") (pin "K") (pinfunction "K_K") (pintype "passive"))
      (node (ref "VD13") (pin "K") (pinfunction "K_K") (pintype "passive"))
      (node (ref "XT2") (pin "2") (pinfunction "GND_2") (pintype "passive"))
      (node (ref "XT2") (pin "4") (pinfunction "GND_4") (pintype "passive"))
    )
    (net (code "48") (name "Net-(IC20B-RBIAS)") (class "Default")
      (node (ref "IC20") (pin "63") (pinfunction "RBIAS_63") (pintype "input"))
      (node (ref "R133") (pin "1") (pinfunction "1_1") (pintype "passive"))
    )
    (net (code "49") (name "Net-(IC20B-SUSP_IND{slash}LOCAL_PWR{slash}NON_REM0)") (class "Default")
      (node (ref "IC20") (pin "45") (pinfunction "SUSP_IND/LOCAL_PWR/NON_REM0_45") (pintype "bidirectional"))
      (node (ref "R134") (pin "1") (pinfunction "1_1") (pintype "passive"))
    )
    (net (code "50") (name "Net-(IC20B-VBUS_DET)") (class "Default")
      (node (ref "IC20") (pin "44") (pinfunction "VBUS_DET_44") (pintype "input"))
      (node (ref "R129") (pin "2") (pinfunction "2_2") (pintype "passive"))
    )
    (net (code "51") (name "Net-(IC20B-VDD18)") (class "Default")
      (node (ref "C76") (pin "2") (pinfunction "2_2") (pintype "passive"))
      (node (ref "C77") (pin "1") (pinfunction "1_1") (pintype "passive"))
      (node (ref "IC20") (pin "25") (pinfunction "VDD18_25") (pintype "power_in"))
    )
    (net (code "52") (name "Net-(IC20B-VDD18PLL)") (class "Default")
      (node (ref "C71") (pin "2") (pinfunction "2_2") (pintype "passive"))
      (node (ref "C72") (pin "1") (pinfunction "1_1") (pintype "passive"))
      (node (ref "IC20") (pin "62") (pinfunction "VDD18PLL_62") (pintype "power_in"))
    )
    (net (code "53") (name "Net-(IC20B-XTAL1{slash}CLKIN)") (class "Default")
      (node (ref "C74") (pin "2") (pinfunction "2_2") (pintype "passive"))
      (node (ref "IC20") (pin "61") (pinfunction "XTAL1/CLKIN_61") (pintype "input"))
      (node (ref "R135") (pin "1") (pinfunction "1_1") (pintype "passive"))
      (node (ref "XT2") (pin "1") (pinfunction "X_1") (pintype "passive"))
    )
    (net (code "54") (name "Net-(IC20B-XTAL2)") (class "Default")
      (node (ref "C75") (pin "2") (pinfunction "2_2") (pintype "passive"))
      (node (ref "IC20") (pin "60") (pinfunction "XTAL2_60") (pintype "bidirectional"))
      (node (ref "R135") (pin "2") (pinfunction "2_2") (pintype "passive"))
      (node (ref "XT2") (pin "3") (pinfunction "X_3") (pintype "passive"))
    )
    (net (code "55") (name "Net-(IC21-SEL)") (class "Default")
      (node (ref "IC21") (pin "10") (pinfunction "SEL_10") (pintype "input"))
      (node (ref "R145") (pin "1") (pinfunction "1_1") (pintype "passive"))
      (node (ref "R149") (pin "2") (pinfunction "2_2") (pintype "passive"))
      (node (ref "R150") (pin "1") (pinfunction "1_1") (pintype "passive"))
    )
    (net (code "56") (name "Net-(IC24-CSLEW)") (class "Default")
      (node (ref "C92") (pin "1") (pinfunction "1_1") (pintype "passive"))
      (node (ref "IC24") (pin "5") (pinfunction "CSLEW_5") (pintype "output"))
      (node (ref "R158") (pin "1") (pinfunction "1_1") (pintype "passive"))
      (node (ref "R159") (pin "2") (pinfunction "2_2") (pintype "passive"))
    )
    (net (code "57") (name "Net-(IC24-EN)") (class "Default")
      (node (ref "IC24") (pin "3") (pinfunction "EN_3") (pintype "input"))
      (node (ref "R156") (pin "1") (pinfunction "1_1") (pintype "passive"))
      (node (ref "R157") (pin "1") (pinfunction "1_1") (pintype "passive"))
    )
    (net (code "58") (name "Net-(IC24-FAULT{slash})") (class "Default")
      (node (ref "IC24") (pin "4") (pinfunction "FAULT/_4") (pintype "output"))
      (node (ref "R160") (pin "1") (pinfunction "1_1") (pintype "passive"))
    )
    (net (code "59") (name "USB_VBUS_IN") (class "Default")
      (node (ref "J29") (pin "A4") (pinfunction "VBUS_A4") (pintype "passive"))
      (node (ref "J29") (pin "A9") (pinfunction "VBUS_A9") (pintype "passive"))
      (node (ref "J29") (pin "B4") (pinfunction "VBUS_B4") (pintype "passive"))
      (node (ref "J29") (pin "B9") (pinfunction "VBUS_B9") (pintype "passive"))
      (node (ref "R139") (pin "2") (pinfunction "2_2") (pintype "passive"))
      (node (ref "VD9") (pin "K") (pinfunction "K_K") (pintype "passive"))
    )
    (net (code "60") (name "VCC3P3") (class "Default")
      (node (ref "C73") (pin "1") (pinfunction "1_1") (pintype "passive"))
      (node (ref "C78") (pin "2") (pinfunction "2_2") (pintype "passive"))
      (node (ref "C79") (pin "1") (pinfunction "1_1") (pintype "passive"))
      (node (ref "C80") (pin "1") (pinfunction "1_1") (pintype "passive"))
      (node (ref "C81") (pin "1") (pinfunction "1_1") (pintype "passive"))
      (node (ref "C82") (pin "1") (pinfunction "1_1") (pintype "passive"))
      (node (ref "C83") (pin "1") (pinfunction "1_1") (pintype "passive"))
      (node (ref "C84") (pin "1") (pinfunction "1_1") (pintype "passive"))
      (node (ref "C85") (pin "2") (pinfunction "2_2") (pintype "passive"))
      (node (ref "C86") (pin "1") (pinfunction "1_1") (pintype "passive"))
      (node (ref "C87") (pin "1") (pinfunction "1_1") (pintype "passive"))
      (node (ref "IC20") (pin "10") (pinfunction "VDDA33_10") (pintype "power_in"))
      (node (ref "IC20") (pin "24") (pinfunction "VDD33CR_24") (pintype "power_in"))
      (node (ref "IC20") (pin "46") (pinfunction "VDD33_46") (pintype "power_in"))
      (node (ref "IC20") (pin "5") (pinfunction "VDDA33_5") (pintype "power_in"))
      (node (ref "IC20") (pin "52") (pinfunction "VDDA33_52") (pintype "power_in"))
      (node (ref "IC20") (pin "57") (pinfunction "VDDA33_57") (pintype "power_in"))
      (node (ref "IC20") (pin "64") (pinfunction "VDD33PLL_64") (pintype "power_in"))
      (node (ref "IC21") (pin "9") (pinfunction "VCC_9") (pintype "power_in"))
      (node (ref "IC22") (pin "8") (pinfunction "VCC_8") (pintype "passive"))
      (node (ref "IC23") (pin "8") (pinfunction "VCC_8") (pintype "power_in"))
      (node (ref "R128") (pin "2") (pinfunction "2_2") (pintype "passive"))
      (node (ref "R129") (pin "1") (pinfunction "1_1") (pintype "passive"))
      (node (ref "R131") (pin "2") (pinfunction "2_2") (pintype "passive"))
      (node (ref "R134") (pin "2") (pinfunction "2_2") (pintype "passive"))
      (node (ref "R141") (pin "2") (pinfunction "2_2") (pintype "passive"))
      (node (ref "R142") (pin "2") (pinfunction "2_2") (pintype "passive"))
      (node (ref "R143") (pin "2") (pinfunction "2_2") (pintype "passive"))
    )
    (net (code "61") (name "VCC5P0") (class "Default")
      (node (ref "C89") (pin "1") (pinfunction "1_1") (pintype "passive"))
      (node (ref "C92") (pin "2") (pinfunction "2_2") (pintype "passive"))
      (node (ref "IC24") (pin "1") (pinfunction "VIN_1") (pintype "input"))
      (node (ref "J32") (pin "4") (pinfunction "4_4") (pintype "passive"))
      (node (ref "R140") (pin "2") (pinfunction "2_2") (pintype "passive"))
      (node (ref "R155") (pin "2") (pinfunction "2_2") (pintype "passive"))
      (node (ref "R156") (pin "2") (pinfunction "2_2") (pintype "passive"))
      (node (ref "VD9") (pin "A") (pinfunction "A_A") (pintype "passive"))
    )
    (net (code "62") (name "VCC5P0_USB3H") (class "Default")
      (node (ref "C88") (pin "2") (pinfunction "2_2") (pintype "passive"))
      (node (ref "C90") (pin "1") (pinfunction "1_1") (pintype "passive"))
      (node (ref "C91") (pin "2") (pinfunction "2_2") (pintype "passive"))
      (node (ref "IC24") (pin "6") (pinfunction "VOUT_6") (pintype "output"))
      (node (ref "J31") (pin "18") (pinfunction "18_18") (pintype "passive"))
      (node (ref "J31") (pin "19") (pinfunction "19_19") (pintype "passive"))
      (node (ref "R155") (pin "1") (pinfunction "1_1") (pintype "passive"))
      (node (ref "R158") (pin "2") (pinfunction "2_2") (pintype "passive"))
    )
    (net (code "63") (name "unconnected-(IC20A-LED_A1_N{slash}PRT_SWP1-Pad51)") (class "Default")
      (node (ref "IC20") (pin "51") (pinfunction "LED_A1_N/PRT_SWP1_51") (pintype "passive+no_connect"))
    )
    (net (code "64") (name "unconnected-(IC20A-LED_A2_N{slash}PRT_SWP2-Pad49)") (class "Default")
      (node (ref "IC20") (pin "49") (pinfunction "LED_A2_N/PRT_SWP2_49") (pintype "passive+no_connect"))
    )
    (net (code "65") (name "unconnected-(IC20A-LED_A3_N{slash}PRT_SWP3-Pad47)") (class "Default")
      (node (ref "IC20") (pin "47") (pinfunction "LED_A3_N/PRT_SWP3_47") (pintype "passive+no_connect"))
    )
    (net (code "66") (name "unconnected-(IC20A-LED_A4_N{slash}PRT_SWP4-Pad33)") (class "Default")
      (node (ref "IC20") (pin "33") (pinfunction "LED_A4_N/PRT_SWP4_33") (pintype "passive+no_connect"))
    )
    (net (code "67") (name "unconnected-(IC20A-LED_A5_N{slash}PRT_SWP5-Pad31)") (class "Default")
      (node (ref "IC20") (pin "31") (pinfunction "LED_A5_N/PRT_SWP5_31") (pintype "passive+no_connect"))
    )
    (net (code "68") (name "unconnected-(IC20A-LED_A6_N{slash}PRT_SWP6-Pad17)") (class "Default")
      (node (ref "IC20") (pin "17") (pinfunction "LED_A6_N/PRT_SWP6_17") (pintype "output+no_connect"))
    )
    (net (code "69") (name "unconnected-(IC20A-LED_A7_N{slash}PRT_SWP7-Pad15)") (class "Default")
      (node (ref "IC20") (pin "15") (pinfunction "LED_A7_N/PRT_SWP7_15") (pintype "output+no_connect"))
    )
    (net (code "70") (name "unconnected-(IC20A-LED_B1_N{slash}BOOST0-Pad50)") (class "Default")
      (node (ref "IC20") (pin "50") (pinfunction "LED_B1_N/BOOST0_50") (pintype "passive+no_connect"))
    )
    (net (code "71") (name "unconnected-(IC20A-LED_B2_N{slash}BOOST1-Pad48)") (class "Default")
      (node (ref "IC20") (pin "48") (pinfunction "LED_B2_N/BOOST1_48") (pintype "passive+no_connect"))
    )
    (net (code "72") (name "unconnected-(IC20A-LED_B3_N{slash}GANG_EN-Pad34)") (class "Default")
      (node (ref "IC20") (pin "34") (pinfunction "LED_B3_N/GANG_EN_34") (pintype "passive+no_connect"))
    )
    (net (code "73") (name "unconnected-(IC20A-LED_B4_N-Pad32)") (class "Default")
      (node (ref "IC20") (pin "32") (pinfunction "LED_B4_N_32") (pintype "passive+no_connect"))
    )
    (net (code "74") (name "unconnected-(IC20A-LED_B5_N-Pad18)") (class "Default")
      (node (ref "IC20") (pin "18") (pinfunction "LED_B5_N_18") (pintype "output+no_connect"))
    )
    (net (code "75") (name "unconnected-(IC20A-LED_B6_N-Pad16)") (class "Default")
      (node (ref "IC20") (pin "16") (pinfunction "LED_B6_N_16") (pintype "output+no_connect"))
    )
    (net (code "76") (name "unconnected-(IC20A-LED_B7_N-Pad14)") (class "Default")
      (node (ref "IC20") (pin "14") (pinfunction "LED_B7_N_14") (pintype "output+no_connect"))
    )
    (net (code "77") (name "unconnected-(IC20A-OCS1_N-Pad28)") (class "Default")
      (node (ref "IC20") (pin "28") (pinfunction "OCS1_N_28") (pintype "passive+no_connect"))
    )
    (net (code "78") (name "unconnected-(IC20A-OCS6_N-Pad38)") (class "Default")
      (node (ref "IC20") (pin "38") (pinfunction "OCS6_N_38") (pintype "passive+no_connect"))
    )
    (net (code "79") (name "unconnected-(IC20A-OCS7_N-Pad37)") (class "Default")
      (node (ref "IC20") (pin "37") (pinfunction "OCS7_N_37") (pintype "passive+no_connect"))
    )
    (net (code "80") (name "unconnected-(IC20A-PRTPWR1-Pad29)") (class "Default")
      (node (ref "IC20") (pin "29") (pinfunction "PRTPWR1_29") (pintype "passive+no_connect"))
    )
    (net (code "81") (name "unconnected-(IC20A-PRTPWR2-Pad26)") (class "Default")
      (node (ref "IC20") (pin "26") (pinfunction "PRTPWR2_26") (pintype "passive+no_connect"))
    )
    (net (code "82") (name "unconnected-(IC20A-PRTPWR3-Pad23)") (class "Default")
      (node (ref "IC20") (pin "23") (pinfunction "PRTPWR3_23") (pintype "passive+no_connect"))
    )
    (net (code "83") (name "unconnected-(IC20A-PRTPWR6-Pad39)") (class "Default")
      (node (ref "IC20") (pin "39") (pinfunction "PRTPWR6_39") (pintype "passive+no_connect"))
    )
    (net (code "84") (name "unconnected-(IC20A-PRTPWR7-Pad36)") (class "Default")
      (node (ref "IC20") (pin "36") (pinfunction "PRTPWR7_36") (pintype "passive+no_connect"))
    )
    (net (code "85") (name "unconnected-(IC20A-USBDN7_DM{slash}PRT_DIS_M7-Pad55)") (class "Default")
      (node (ref "IC20") (pin "55") (pinfunction "USBDN7_DM/PRT_DIS_M7_55") (pintype "bidirectional+no_connect"))
    )
    (net (code "86") (name "unconnected-(IC20A-USBDN7_DP{slash}PRT_DIS_P7-Pad56)") (class "Default")
      (node (ref "IC20") (pin "56") (pinfunction "USBDN7_DP/PRT_DIS_P7_56") (pintype "bidirectional+no_connect"))
    )
    (net (code "87") (name "unconnected-(J29-SBU1-PadA8)") (class "Default")
      (node (ref "J29") (pin "A8") (pinfunction "SBU1_A8") (pintype "passive+no_connect"))
    )
    (net (code "88") (name "unconnected-(J29-SBU2-PadB8)") (class "Default")
      (node (ref "J29") (pin "B8") (pinfunction "SBU2_B8") (pintype "passive+no_connect"))
    )
    (net (code "89") (name "unconnected-(J29-SSRXn1-PadB10)") (class "Default")
      (node (ref "J29") (pin "B10") (pinfunction "SSRXn1_B10") (pintype "passive+no_connect"))
    )
    (net (code "90") (name "unconnected-(J29-SSRXn2-PadA10)") (class "Default")
      (node (ref "J29") (pin "A10") (pinfunction "SSRXn2_A10") (pintype "passive+no_connect"))
    )
    (net (code "91") (name "unconnected-(J29-SSRXp1-PadB11)") (class "Default")
      (node (ref "J29") (pin "B11") (pinfunction "SSRXp1_B11") (pintype "passive+no_connect"))
    )
    (net (code "92") (name "unconnected-(J29-SSRXp2-PadA11)") (class "Default")
      (node (ref "J29") (pin "A11") (pinfunction "SSRXp2_A11") (pintype "passive+no_connect"))
    )
    (net (code "93") (name "unconnected-(J29-SSTXn1-PadA3)") (class "Default")
      (node (ref "J29") (pin "A3") (pinfunction "SSTXn1_A3") (pintype "passive+no_connect"))
    )
    (net (code "94") (name "unconnected-(J29-SSTXn2-PadB3)") (class "Default")
      (node (ref "J29") (pin "B3") (pinfunction "SSTXn2_B3") (pintype "passive+no_connect"))
    )
    (net (code "95") (name "unconnected-(J29-SSTXp1-PadA2)") (class "Default")
      (node (ref "J29") (pin "A2") (pinfunction "SSTXp1_A2") (pintype "passive+no_connect"))
    )
    (net (code "96") (name "unconnected-(J29-SSTXp2-PadB2)") (class "Default")
      (node (ref "J29") (pin "B2") (pinfunction "SSTXp2_B2") (pintype "passive+no_connect"))
    )
    (net (code "97") (name "unconnected-(J31-Pad1)") (class "Default")
      (node (ref "J31") (pin "1") (pinfunction "1_1") (pintype "passive+no_connect"))
    )
    (net (code "98") (name "unconnected-(J31-Pad8)") (class "Default")
      (node (ref "J31") (pin "8") (pinfunction "8_8") (pintype "passive+no_connect"))
    )
    (net (code "99") (name "unconnected-(J31-Pad10)") (class "Default")
      (node (ref "J31") (pin "10") (pinfunction "10_10") (pintype "passive+no_connect"))
    )
    (net (code "100") (name "unconnected-(J31-Pad14)") (class "Default")
      (node (ref "J31") (pin "14") (pinfunction "14_14") (pintype "passive+no_connect"))
    )
    (net (code "101") (name "unconnected-(J31-Pad16)") (class "Default")
      (node (ref "J31") (pin "16") (pinfunction "16_16") (pintype "passive+no_connect"))
    )
    (net (code "102") (name "unconnected-(J31-Pad20)") (class "Default")
      (node (ref "J31") (pin "20") (pinfunction "20_20") (pintype "passive+no_connect"))
    )
    (net (code "103") (name "unconnected-(JMP1-Pad1)") (class "Default")
      (node (ref "JMP1") (pin "1") (pinfunction "1_1") (pintype "passive"))
    )
    (net (code "104") (name "unconnected-(JMP1-Pad2)") (class "Default")
      (node (ref "JMP1") (pin "2") (pinfunction "2_2") (pintype "passive"))
    )
  )
)
